# SML-230109PCB1__PWR.net
KiCad netlist of a schematic drawn in Altium Designer
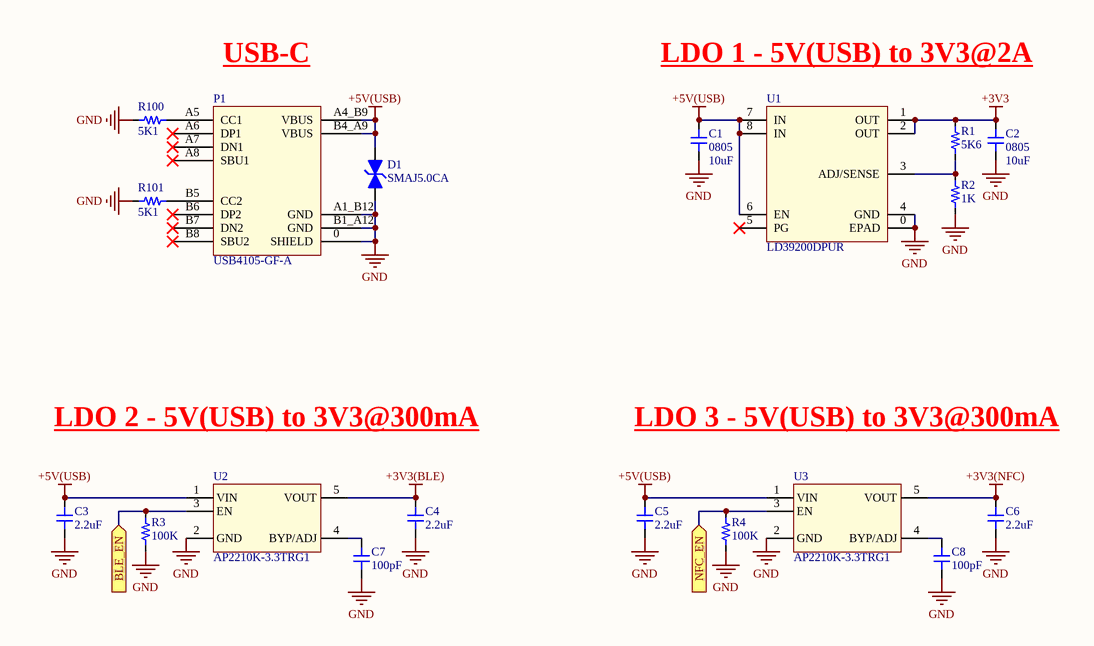
[diagram p0: SML-230109PCB1__PWR.SchDoc]

(export (version "E")
  (design (tool "Eeschema 10.0.6"))
  (components
    (comp (ref "C1")
      (value "10uF")
      (footprint "[G] CAP-MLCC__0805")
      (description "CAP MLCC 0805")
      (fields
        (field (name "VOLTAGE") "010")
        (field (name "[06] - PACKAGE") "0805")
        (field (name "Comment") ".")
      )
      (libsource (lib "DEB_LIB_SCH_22-03") (part "CAP_MLCC_0805"))
    )
    (comp (ref "C2")
      (value "10uF")
      (footprint "[G] CAP-MLCC__0805")
      (description "CAP MLCC 0805")
      (fields
        (field (name "VOLTAGE") "010")
        (field (name "[06] - PACKAGE") "0805")
        (field (name "Comment") ".")
      )
      (libsource (lib "DEB_LIB_SCH_22-03") (part "CAP_MLCC_0805"))
    )
    (comp (ref "C3")
      (value "2.2uF")
      (footprint "[G] CAP-MLCC__0603")
      (description "CAP MLCC 0603")
      (fields (field (name "VOLTAGE") "010") (field (name "Comment") "."))
      (libsource (lib "DEB_LIB_SCH_22-03") (part "CAP_MLCC_0603"))
    )
    (comp (ref "C4")
      (value "2.2uF")
      (footprint "[G] CAP-MLCC__0603")
      (description "CAP MLCC 0603")
      (fields (field (name "VOLTAGE") "010") (field (name "Comment") "."))
      (libsource (lib "DEB_LIB_SCH_22-03") (part "CAP_MLCC_0603"))
    )
    (comp (ref "C5")
      (value "2.2uF")
      (footprint "[G] CAP-MLCC__0603")
      (description "CAP MLCC 0603")
      (fields (field (name "VOLTAGE") "010") (field (name "Comment") "."))
      (libsource (lib "DEB_LIB_SCH_22-03") (part "CAP_MLCC_0603"))
    )
    (comp (ref "C6")
      (value "2.2uF")
      (footprint "[G] CAP-MLCC__0603")
      (description "CAP MLCC 0603")
      (fields (field (name "VOLTAGE") "010") (field (name "Comment") "."))
      (libsource (lib "DEB_LIB_SCH_22-03") (part "CAP_MLCC_0603"))
    )
    (comp (ref "C7")
      (value "100pF")
      (footprint "[G] CAP-MLCC__0603")
      (description "CAP MLCC 0603")
      (fields (field (name "VOLTAGE") "010") (field (name "Comment") "."))
      (libsource (lib "DEB_LIB_SCH_22-03") (part "CAP_MLCC_0603"))
    )
    (comp (ref "C8")
      (value "100pF")
      (footprint "[G] CAP-MLCC__0603")
      (description "CAP MLCC 0603")
      (fields (field (name "VOLTAGE") "010") (field (name "Comment") "."))
      (libsource (lib "DEB_LIB_SCH_22-03") (part "CAP_MLCC_0603"))
    )
    (comp (ref "D1")
      (value ".")
      (footprint "[G] SMA(DO-214AC)__W/O")
      (description "DIODE TVS, SMA (DO-214AC), Vr=5V, Vbr=6'4V, Vc=9'2V, Ipp=43'5A, Pppm=400W")
      (fields (field (name "[01] - MPN CODE") "SMAJ5.0CA"))
      (libsource (lib "DEB_LIB_SCH_22-03") (part "SMAJ5.0CA"))
    )
    (comp (ref "P1")
      (value ".")
      (footprint "CONN-USB-C__USB4105-GF-A")
      (description "CONN USB TYPE C, smd/th, right angle")
      (fields (field (name "[01] - MPN CODE") "USB4105-GF-A"))
      (libsource (lib "DEB_LIB_SCH_22-03") (part "USB4105-GF-A"))
    )
    (comp (ref "R1")
      (value "5K6")
      (footprint "[G] RES-CHIP__0603")
      (description "RES SMD 0603 [G]")
      (fields (field (name "TOLERANCE") "1%") (field (name "Comment") "."))
      (libsource (lib "DEB_LIB_SCH_22-03") (part "RES_SMD_0603"))
    )
    (comp (ref "R2")
      (value "1K")
      (footprint "[G] RES-CHIP__0603")
      (description "RES SMD 0603 [G]")
      (fields (field (name "TOLERANCE") "1%") (field (name "Comment") "."))
      (libsource (lib "DEB_LIB_SCH_22-03") (part "RES_SMD_0603"))
    )
    (comp (ref "R3")
      (value "100K")
      (footprint "[G] RES-CHIP__0603")
      (description "RES SMD 0603 [G]")
      (fields (field (name "TOLERANCE") "1%") (field (name "Comment") "."))
      (libsource (lib "DEB_LIB_SCH_22-03") (part "RES_SMD_0603"))
    )
    (comp (ref "R4")
      (value "100K")
      (footprint "[G] RES-CHIP__0603")
      (description "RES SMD 0603 [G]")
      (fields (field (name "TOLERANCE") "1%") (field (name "Comment") "."))
      (libsource (lib "DEB_LIB_SCH_22-03") (part "RES_SMD_0603"))
    )
    (comp (ref "R100")
      (value "5K1")
      (footprint "[G] RES-CHIP__0402")
      (description "RES SMD 0402 [G]")
      (fields (field (name "TOLERANCE") "1%") (field (name "Comment") "."))
      (libsource (lib "DEB_LIB_SCH_22-03") (part "RES_SMD_0402"))
    )
    (comp (ref "R101")
      (value "5K1")
      (footprint "[G] RES-CHIP__0402")
      (description "RES SMD 0402 [G]")
      (fields (field (name "TOLERANCE") "1%") (field (name "Comment") "."))
      (libsource (lib "DEB_LIB_SCH_22-03") (part "RES_SMD_0402"))
    )
    (comp (ref "U1")
      (value ".")
      (footprint "PMIC-LDO__LD39200DPUR__DFN-8(4X4)")
      (description "PMIC LDO, DFN-8, Vout=ADJ, Iout=2000A, Vin=1'25-6'0V, Vdrop-max=130mV, Iq-max=1mA")
      (fields (field (name "[01] - MPN CODE") "LD39200DPUR"))
      (libsource (lib "DEB_LIB_SCH_22-03") (part "LD39200DPUR"))
    )
    (comp (ref "U2")
      (value ".")
      (footprint "[G] SOT23-5")
      (description "PMIC LDO, SOT23-5, Vout=3'3V, Iout=300mA, Vin=2'5-13'2V, Vdrop-max=250mV, Iq-max=4mA")
      (fields (field (name "[01] - MPN CODE") "AP2210K-3.3TRG1"))
      (libsource (lib "DEB_LIB_SCH_22-03") (part "AP2210K-3.3TRG1"))
    )
    (comp (ref "U3")
      (value ".")
      (footprint "[G] SOT23-5")
      (description "PMIC LDO, SOT23-5, Vout=3'3V, Iout=300mA, Vin=2'5-13'2V, Vdrop-max=250mV, Iq-max=4mA")
      (fields (field (name "[01] - MPN CODE") "AP2210K-3.3TRG1"))
      (libsource (lib "DEB_LIB_SCH_22-03") (part "AP2210K-3.3TRG1"))
    )
  )
  (nets
    (net (code "1") (name "+3V3") (class "Default")
      (node (ref "C2") (pin "2") (pinfunction "2_2") (pintype "passive"))
      (node (ref "R1") (pin "2") (pinfunction "2_2") (pintype "passive"))
      (node (ref "U1") (pin "1") (pinfunction "OUT_1") (pintype "passive"))
      (node (ref "U1") (pin "2") (pinfunction "OUT_2") (pintype "passive"))
    )
    (net (code "2") (name "+3V3(BLE)") (class "Default")
      (node (ref "C4") (pin "2") (pinfunction "2_2") (pintype "passive"))
      (node (ref "U2") (pin "5") (pinfunction "VOUT_5") (pintype "passive"))
    )
    (net (code "3") (name "+3V3(NFC)") (class "Default")
      (node (ref "C6") (pin "2") (pinfunction "2_2") (pintype "passive"))
      (node (ref "U3") (pin "5") (pinfunction "VOUT_5") (pintype "passive"))
    )
    (net (code "4") (name "+5V(USB)") (class "Default")
      (node (ref "C1") (pin "2") (pinfunction "2_2") (pintype "passive"))
      (node (ref "C3") (pin "2") (pinfunction "2_2") (pintype "passive"))
      (node (ref "C5") (pin "2") (pinfunction "2_2") (pintype "passive"))
      (node (ref "D1") (pin "K") (pinfunction "K_K") (pintype "passive"))
      (node (ref "P1") (pin "A4_B9") (pinfunction "VBUS_A4_B9") (pintype "passive"))
      (node (ref "P1") (pin "B4_A9") (pinfunction "VBUS_B4_A9") (pintype "passive"))
      (node (ref "U1") (pin "6") (pinfunction "EN_6") (pintype "passive"))
      (node (ref "U1") (pin "7") (pinfunction "IN_7") (pintype "passive"))
      (node (ref "U1") (pin "8") (pinfunction "IN_8") (pintype "passive"))
      (node (ref "U2") (pin "1") (pinfunction "VIN_1") (pintype "passive"))
      (node (ref "U3") (pin "1") (pinfunction "VIN_1") (pintype "passive"))
    )
    (net (code "5") (name "/BLE_EN") (class "Default")
      (node (ref "R3") (pin "2") (pinfunction "2_2") (pintype "passive"))
      (node (ref "U2") (pin "3") (pinfunction "EN_3") (pintype "passive"))
    )
    (net (code "6") (name "/NFC_EN") (class "Default")
      (node (ref "R4") (pin "2") (pinfunction "2_2") (pintype "passive"))
      (node (ref "U3") (pin "3") (pinfunction "EN_3") (pintype "passive"))
    )
    (net (code "7") (name "GND") (class "Default")
      (node (ref "C1") (pin "1") (pinfunction "1_1") (pintype "passive"))
      (node (ref "C2") (pin "1") (pinfunction "1_1") (pintype "passive"))
      (node (ref "C3") (pin "1") (pinfunction "1_1") (pintype "passive"))
      (node (ref "C4") (pin "1") (pinfunction "1_1") (pintype "passive"))
      (node (ref "C5") (pin "1") (pinfunction "1_1") (pintype "passive"))
      (node (ref "C6") (pin "1") (pinfunction "1_1") (pintype "passive"))
      (node (ref "C7") (pin "1") (pinfunction "1_1") (pintype "passive"))
      (node (ref "C8") (pin "1") (pinfunction "1_1") (pintype "passive"))
      (node (ref "D1") (pin "A") (pinfunction "A_A") (pintype "passive"))
      (node (ref "P1") (pin "0") (pinfunction "SHIELD_0") (pintype "passive"))
      (node (ref "P1") (pin "A1_B12") (pinfunction "GND_A1_B12") (pintype "passive"))
      (node (ref "P1") (pin "B1_A12") (pinfunction "GND_B1_A12") (pintype "passive"))
      (node (ref "R100") (pin "1") (pinfunction "1_1") (pintype "passive"))
      (node (ref "R101") (pin "1") (pinfunction "1_1") (pintype "passive"))
      (node (ref "R2") (pin "1") (pinfunction "1_1") (pintype "passive"))
      (node (ref "R3") (pin "1") (pinfunction "1_1") (pintype "passive"))
      (node (ref "R4") (pin "1") (pinfunction "1_1") (pintype "passive"))
      (node (ref "U1") (pin "0") (pinfunction "EPAD_0") (pintype "passive"))
      (node (ref "U1") (pin "4") (pinfunction "GND_4") (pintype "passive"))
      (node (ref "U2") (pin "2") (pinfunction "GND_2") (pintype "passive"))
      (node (ref "U3") (pin "2") (pinfunction "GND_2") (pintype "passive"))
    )
    (net (code "8") (name "Net-(P1-CC1)") (class "Default")
      (node (ref "P1") (pin "A5") (pinfunction "CC1_A5") (pintype "passive"))
      (node (ref "R100") (pin "2") (pinfunction "2_2") (pintype "passive"))
    )
    (net (code "9") (name "Net-(P1-CC2)") (class "Default")
      (node (ref "P1") (pin "B5") (pinfunction "CC2_B5") (pintype "passive"))
      (node (ref "R101") (pin "2") (pinfunction "2_2") (pintype "passive"))
    )
    (net (code "10") (name "Net-(U1-ADJ{slash}SENSE)") (class "Default")
      (node (ref "R1") (pin "1") (pinfunction "1_1") (pintype "passive"))
      (node (ref "R2") (pin "2") (pinfunction "2_2") (pintype "passive"))
      (node (ref "U1") (pin "3") (pinfunction "ADJ/SENSE_3") (pintype "passive"))
    )
    (net (code "11") (name "Net-(U2-BYP{slash}ADJ)") (class "Default")
      (node (ref "C7") (pin "2") (pinfunction "2_2") (pintype "passive"))
      (node (ref "U2") (pin "4") (pinfunction "BYP/ADJ_4") (pintype "passive"))
    )
    (net (code "12") (name "Net-(U3-BYP{slash}ADJ)") (class "Default")
      (node (ref "C8") (pin "2") (pinfunction "2_2") (pintype "passive"))
      (node (ref "U3") (pin "4") (pinfunction "BYP/ADJ_4") (pintype "passive"))
    )
    (net (code "13") (name "unconnected-(P1-DN1-PadA7)") (class "Default")
      (node (ref "P1") (pin "A7") (pinfunction "DN1_A7") (pintype "passive+no_connect"))
    )
    (net (code "14") (name "unconnected-(P1-DN2-PadB7)") (class "Default")
      (node (ref "P1") (pin "B7") (pinfunction "DN2_B7") (pintype "passive+no_connect"))
    )
    (net (code "15") (name "unconnected-(P1-DP1-PadA6)") (class "Default")
      (node (ref "P1") (pin "A6") (pinfunction "DP1_A6") (pintype "passive+no_connect"))
    )
    (net (code "16") (name "unconnected-(P1-DP2-PadB6)") (class "Default")
      (node (ref "P1") (pin "B6") (pinfunction "DP2_B6") (pintype "passive+no_connect"))
    )
    (net (code "17") (name "unconnected-(P1-SBU1-PadA8)") (class "Default")
      (node (ref "P1") (pin "A8") (pinfunction "SBU1_A8") (pintype "passive+no_connect"))
    )
    (net (code "18") (name "unconnected-(P1-SBU2-PadB8)") (class "Default")
      (node (ref "P1") (pin "B8") (pinfunction "SBU2_B8") (pintype "passive+no_connect"))
    )
    (net (code "19") (name "unconnected-(U1-PG-Pad5)") (class "Default")
      (node (ref "U1") (pin "5") (pinfunction "PG_5") (pintype "passive+no_connect"))
    )
  )
)
